# k1fm_wspr_tx-1_0.net
KiCad netlist of a schematic drawn in EAGLE
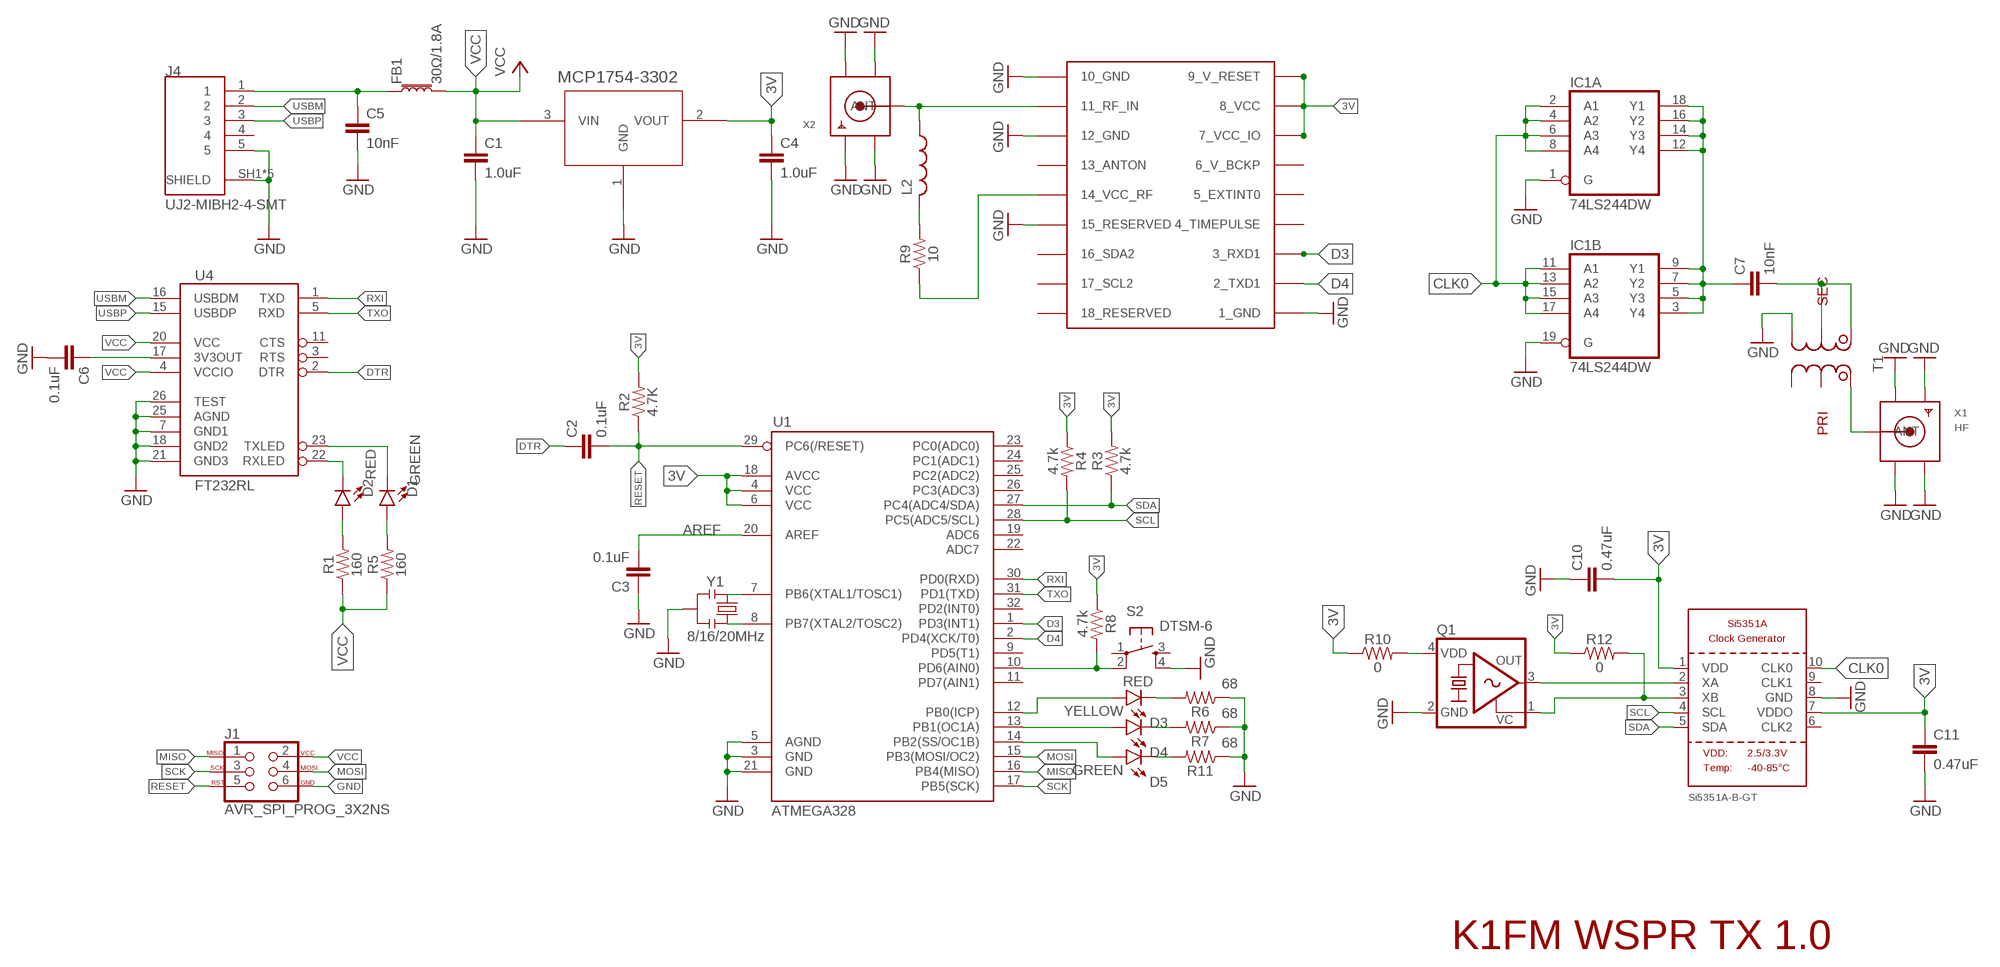
[diagram p0: schematic, sheet 1]

(export (version "E")
  (design (tool "Eeschema 10.0.6"))
  (components
    (comp (ref "C1")
      (value "1.0uF")
      (footprint "eagle-import:0603")
      (libsource (lib "eagle-import") (part "1.0UF-0603-16V-10%"))
    )
    (comp (ref "C2")
      (value "0.1uF")
      (footprint "eagle-import:0603")
      (libsource (lib "eagle-import") (part "0.1UF-0603-25V-5%"))
    )
    (comp (ref "C3")
      (value "0.1uF")
      (footprint "eagle-import:0603")
      (libsource (lib "eagle-import") (part "0.1UF-0603-25V-5%"))
    )
    (comp (ref "C4")
      (value "1.0uF")
      (footprint "eagle-import:0603")
      (libsource (lib "eagle-import") (part "1.0UF-0603-16V-10%"))
    )
    (comp (ref "C5")
      (value "10nF")
      (footprint "eagle-import:0603")
      (libsource (lib "eagle-import") (part "1.0UF-0603-16V-10%"))
    )
    (comp (ref "C6")
      (value "0.1uF")
      (footprint "eagle-import:0603")
      (libsource (lib "eagle-import") (part "0.1UF-0603-25V-5%"))
    )
    (comp (ref "C7")
      (value "10nF")
      (footprint "eagle-import:0603")
      (libsource (lib "eagle-import") (part "1.0UF-0603-16V-10%"))
    )
    (comp (ref "C10")
      (value "0.47uF")
      (footprint "eagle-import:0603")
      (libsource (lib "eagle-import") (part "0.1UF-0603-25V-5%"))
    )
    (comp (ref "C11")
      (value "0.47uF")
      (footprint "eagle-import:0603")
      (libsource (lib "eagle-import") (part "0.1UF-0603-25V-5%"))
    )
    (comp (ref "D1")
      (value "GREEN")
      (footprint "eagle-import:LED-0603")
      (libsource (lib "eagle-import") (part "LED0603"))
    )
    (comp (ref "D2")
      (value "RED")
      (footprint "eagle-import:LED-0603")
      (libsource (lib "eagle-import") (part "LED0603"))
    )
    (comp (ref "D3")
      (value "RED")
      (footprint "eagle-import:LED-0603")
      (libsource (lib "eagle-import") (part "LED0603"))
    )
    (comp (ref "D4")
      (value "YELLOW")
      (footprint "eagle-import:LED-0603")
      (libsource (lib "eagle-import") (part "LED0603"))
    )
    (comp (ref "D5")
      (value "GREEN")
      (footprint "eagle-import:LED-0603")
      (libsource (lib "eagle-import") (part "LED0603"))
    )
    (comp (ref "FB1")
      (value "30Ω/1.8A")
      (footprint "eagle-import:0603")
      (libsource (lib "eagle-import") (part "FERRITE_BEAD-0603"))
    )
    (comp (ref "GPS1")
      (value "UBLOX_MAX")
      (footprint "eagle-import:UBLOX_MAX")
      (libsource (lib "eagle-import") (part "UBLOX_MAX"))
    )
    (comp (ref "IC1")
      (value "74LS244DW")
      (footprint "eagle-import:SO20W")
      (libsource (lib "eagle-import") (part "74244DWLS"))
    )
    (comp (ref "J1")
      (value "AVR_SPI_PROG_3X2NS")
      (footprint "eagle-import:2X3-NS")
      (libsource (lib "eagle-import") (part "AVR_SPI_PROG_3X2NS"))
    )
    (comp (ref "J4")
      (value "UJ2-MIBH2-4-SMT")
      (footprint "eagle-import:CUI_UJ2-MIBH2-4-SMT")
      (fields (field (name "MANUFACTURER") "CUI INC"))
      (libsource (lib "eagle-import") (part "UJ2-MIBH2-4-SMT"))
    )
    (comp (ref "L2")
      (value "INDUCTOR_0402_M")
      (footprint "eagle-import:RESC0402_M")
      (libsource (lib "eagle-import") (part "INDUCTOR_0402_M"))
    )
    (comp (ref "Q1")
      (value "KXO-VCXO-SINE-84")
      (footprint "eagle-import:3.2X2.5_KXO-84")
      (libsource (lib "eagle-import") (part "KXO-VCXO-SINE-84"))
    )
    (comp (ref "R1")
      (value "160")
      (footprint "eagle-import:0603")
      (libsource (lib "eagle-import") (part "4.7KOHM-0603-1/10W-1%"))
    )
    (comp (ref "R2")
      (value "4.7K")
      (footprint "eagle-import:0603")
      (libsource (lib "eagle-import") (part "10KOHM-0603-1/10W-1%"))
    )
    (comp (ref "R3")
      (value "4.7k")
      (footprint "eagle-import:0603")
      (libsource (lib "eagle-import") (part "4.7KOHM-0603-1/10W-1%"))
    )
    (comp (ref "R4")
      (value "4.7k")
      (footprint "eagle-import:0603")
      (libsource (lib "eagle-import") (part "4.7KOHM-0603-1/10W-1%"))
    )
    (comp (ref "R5")
      (value "160")
      (footprint "eagle-import:0603")
      (libsource (lib "eagle-import") (part "4.7KOHM-0603-1/10W-1%"))
    )
    (comp (ref "R6")
      (value "68")
      (footprint "eagle-import:0603")
      (libsource (lib "eagle-import") (part "4.7KOHM-0603-1/10W-1%"))
    )
    (comp (ref "R7")
      (value "68")
      (footprint "eagle-import:0603")
      (libsource (lib "eagle-import") (part "4.7KOHM-0603-1/10W-1%"))
    )
    (comp (ref "R8")
      (value "4.7k")
      (footprint "eagle-import:0603")
      (libsource (lib "eagle-import") (part "4.7KOHM-0603-1/10W-1%"))
    )
    (comp (ref "R9")
      (value "10")
      (footprint "eagle-import:0603")
      (libsource (lib "eagle-import") (part "10KOHM-0603-1/10W-1%"))
    )
    (comp (ref "R10")
      (value "0")
      (footprint "eagle-import:0603")
      (libsource (lib "eagle-import") (part "4.7KOHM-0603-1/10W-1%"))
    )
    (comp (ref "R11")
      (value "68")
      (footprint "eagle-import:0603")
      (libsource (lib "eagle-import") (part "4.7KOHM-0603-1/10W-1%"))
    )
    (comp (ref "R12")
      (value "0")
      (footprint "eagle-import:0603")
      (libsource (lib "eagle-import") (part "4.7KOHM-0603-1/10W-1%"))
    )
    (comp (ref "S2")
      (value "DTSM-6")
      (footprint "eagle-import:DTSM-6")
      (libsource (lib "eagle-import") (part "DTSM-6"))
    )
    (comp (ref "T1")
      (value "TT1-6")
      (footprint "eagle-import:KK81")
      (libsource (lib "eagle-import") (part "TT1-6"))
    )
    (comp (ref "U1")
      (value "ATMEGA328")
      (footprint "eagle-import:TQFP32-08")
      (libsource (lib "eagle-import") (part "ATMEGA168"))
    )
    (comp (ref "U2")
      (value "Si5351A-B-GT")
      (footprint "eagle-import:MSOP10")
      (libsource (lib "eagle-import") (part "SI5351A"))
    )
    (comp (ref "U3")
      (value "MCP1754X-XXXXX/C")
      (footprint "eagle-import:SOT-23A_MC")
      (libsource (lib "eagle-import") (part "MCP1754X-XXXXX/C"))
    )
    (comp (ref "U4")
      (value "FT232RL")
      (footprint "eagle-import:SSOP28DB")
      (libsource (lib "eagle-import") (part "FT232RL-BASICSSOP"))
    )
    (comp (ref "X1")
      (value "HF")
      (footprint "eagle-import:SMA_EDGELAUNCH")
      (libsource (lib "eagle-import") (part "SMACONNECTOR_EDGE"))
    )
    (comp (ref "X2")
      (value "SMACONNECTOR_EDGE")
      (footprint "eagle-import:SMA_EDGELAUNCH")
      (libsource (lib "eagle-import") (part "SMACONNECTOR_EDGE"))
    )
    (comp (ref "Y1")
      (value "8/16/20MHz")
      (footprint "eagle-import:RESONATOR-SMD-1_1")
      (libsource (lib "eagle-import") (part "RESONATOR1{colon}1"))
    )
  )
  (nets
    (net (code "1") (name "/AREF") (class "Default")
      (node (ref "C3") (pin "2") (pinfunction "2_2") (pintype "passive"))
      (node (ref "U1") (pin "20") (pinfunction "AREF_20") (pintype "bidirectional"))
    )
    (net (code "2") (name "3V") (class "Default")
      (node (ref "C10") (pin "2") (pinfunction "2_2") (pintype "passive"))
      (node (ref "C11") (pin "1") (pinfunction "1_1") (pintype "passive"))
      (node (ref "C4") (pin "1") (pinfunction "1_1") (pintype "passive"))
      (node (ref "GPS1") (pin "7_VCC_IO") (pinfunction "7_VCC_IO_7_VCC_IO") (pintype "power_in"))
      (node (ref "GPS1") (pin "8_VCC") (pinfunction "8_VCC_8_VCC") (pintype "power_in"))
      (node (ref "GPS1") (pin "9_V_RESET") (pinfunction "9_V_RESET_9_V_RESET") (pintype "power_in"))
      (node (ref "R10") (pin "1") (pinfunction "1_1") (pintype "passive"))
      (node (ref "R12") (pin "1") (pinfunction "1_1") (pintype "passive"))
      (node (ref "R2") (pin "2") (pinfunction "2_2") (pintype "passive"))
      (node (ref "R3") (pin "2") (pinfunction "2_2") (pintype "passive"))
      (node (ref "R4") (pin "1") (pinfunction "1_1") (pintype "passive"))
      (node (ref "R8") (pin "1") (pinfunction "1_1") (pintype "passive"))
      (node (ref "U1") (pin "18") (pinfunction "AVCC_18") (pintype "bidirectional"))
      (node (ref "U1") (pin "4") (pinfunction "VCC_4") (pintype "bidirectional"))
      (node (ref "U1") (pin "6") (pinfunction "VCC_6") (pintype "bidirectional"))
      (node (ref "U2") (pin "1") (pinfunction "VDD_1") (pintype "power_in"))
      (node (ref "U2") (pin "7") (pinfunction "VDDO_7") (pintype "power_in"))
      (node (ref "U3") (pin "2") (pinfunction "VOUT_2") (pintype "passive"))
    )
    (net (code "3") (name "CLK0") (class "Default")
      (node (ref "IC1") (pin "11") (pinfunction "A1_11") (pintype "input"))
      (node (ref "IC1") (pin "13") (pinfunction "A2_13") (pintype "input"))
      (node (ref "IC1") (pin "15") (pinfunction "A3_15") (pintype "input"))
      (node (ref "IC1") (pin "17") (pinfunction "A4_17") (pintype "input"))
      (node (ref "IC1") (pin "2") (pinfunction "A1_2") (pintype "input"))
      (node (ref "IC1") (pin "4") (pinfunction "A2_4") (pintype "input"))
      (node (ref "IC1") (pin "6") (pinfunction "A3_6") (pintype "input"))
      (node (ref "IC1") (pin "8") (pinfunction "A4_8") (pintype "input"))
      (node (ref "U2") (pin "10") (pinfunction "CLK0_10") (pintype "output"))
    )
    (net (code "4") (name "D3") (class "Default")
      (node (ref "GPS1") (pin "3_RXD1") (pinfunction "3_RXD1_3_RXD1") (pintype "bidirectional"))
      (node (ref "U1") (pin "1") (pinfunction "PD3(INT1)_1") (pintype "bidirectional"))
    )
    (net (code "5") (name "D4") (class "Default")
      (node (ref "GPS1") (pin "2_TXD1") (pinfunction "2_TXD1_2_TXD1") (pintype "bidirectional"))
      (node (ref "U1") (pin "2") (pinfunction "PD4(XCK/T0)_2") (pintype "bidirectional"))
    )
    (net (code "6") (name "DTR") (class "Default")
      (node (ref "C2") (pin "1") (pinfunction "1_1") (pintype "passive"))
      (node (ref "U4") (pin "2") (pinfunction "DTR_2") (pintype "bidirectional"))
    )
    (net (code "7") (name "GND") (class "Default")
      (node (ref "C1") (pin "2") (pinfunction "2_2") (pintype "passive"))
      (node (ref "C10") (pin "1") (pinfunction "1_1") (pintype "passive"))
      (node (ref "C11") (pin "2") (pinfunction "2_2") (pintype "passive"))
      (node (ref "C3") (pin "1") (pinfunction "1_1") (pintype "passive"))
      (node (ref "C4") (pin "2") (pinfunction "2_2") (pintype "passive"))
      (node (ref "C5") (pin "2") (pinfunction "2_2") (pintype "passive"))
      (node (ref "C6") (pin "2") (pinfunction "2_2") (pintype "passive"))
      (node (ref "GPS1") (pin "10_GND") (pinfunction "10_GND_10_GND") (pintype "power_in"))
      (node (ref "GPS1") (pin "12_GND") (pinfunction "12_GND_12_GND") (pintype "power_in"))
      (node (ref "GPS1") (pin "15_RESERVED") (pinfunction "15_RESERVED_15_RESERVED") (pintype "bidirectional"))
      (node (ref "GPS1") (pin "1_GND") (pinfunction "1_GND_1_GND") (pintype "power_in"))
      (node (ref "IC1") (pin "1") (pinfunction "G_1") (pintype "input"))
      (node (ref "IC1") (pin "19") (pinfunction "G_19") (pintype "input"))
      (node (ref "J1") (pin "6") (pinfunction "6_6") (pintype "passive"))
      (node (ref "J4") (pin "5") (pinfunction "5_5") (pintype "passive"))
      (node (ref "J4") (pin "SH1") (pinfunction "SHIELD_SH1") (pintype "passive"))
      (node (ref "J4") (pin "SH2") (pinfunction "SHIELD_SH2") (pintype "passive"))
      (node (ref "J4") (pin "SH3") (pinfunction "SHIELD_SH3") (pintype "passive"))
      (node (ref "J4") (pin "SH4") (pinfunction "SHIELD_SH4") (pintype "passive"))
      (node (ref "J4") (pin "SH5") (pinfunction "SHIELD_SH5") (pintype "passive"))
      (node (ref "Q1") (pin "2") (pinfunction "GND_2") (pintype "power_in"))
      (node (ref "R11") (pin "1") (pinfunction "1_1") (pintype "passive"))
      (node (ref "R6") (pin "1") (pinfunction "1_1") (pintype "passive"))
      (node (ref "R7") (pin "1") (pinfunction "1_1") (pintype "passive"))
      (node (ref "S2") (pin "4") (pinfunction "4_4") (pintype "passive"))
      (node (ref "T1") (pin "1") (pinfunction "S2_1") (pintype "passive"))
      (node (ref "U1") (pin "21") (pinfunction "GND_21") (pintype "bidirectional"))
      (node (ref "U1") (pin "3") (pinfunction "GND_3") (pintype "bidirectional"))
      (node (ref "U1") (pin "5") (pinfunction "AGND_5") (pintype "bidirectional"))
      (node (ref "U2") (pin "8") (pinfunction "GND_8") (pintype "power_in"))
      (node (ref "U3") (pin "1") (pinfunction "GND_1") (pintype "passive"))
      (node (ref "U4") (pin "18") (pinfunction "GND2_18") (pintype "power_in"))
      (node (ref "U4") (pin "21") (pinfunction "GND3_21") (pintype "power_in"))
      (node (ref "U4") (pin "25") (pinfunction "AGND_25") (pintype "power_in"))
      (node (ref "U4") (pin "26") (pinfunction "TEST_26") (pintype "input"))
      (node (ref "U4") (pin "7") (pinfunction "GND1_7") (pintype "power_in"))
      (node (ref "X1") (pin "GND@1") (pinfunction "GND4_GND@1") (pintype "power_in"))
      (node (ref "X1") (pin "GND@2") (pinfunction "GND3_GND@2") (pintype "power_in"))
      (node (ref "X1") (pin "GND@3") (pinfunction "GND2_GND@3") (pintype "power_in"))
      (node (ref "X1") (pin "GND@4") (pinfunction "GND1_GND@4") (pintype "power_in"))
      (node (ref "X2") (pin "GND@1") (pinfunction "GND4_GND@1") (pintype "power_in"))
      (node (ref "X2") (pin "GND@2") (pinfunction "GND3_GND@2") (pintype "power_in"))
      (node (ref "X2") (pin "GND@3") (pinfunction "GND2_GND@3") (pintype "power_in"))
      (node (ref "X2") (pin "GND@4") (pinfunction "GND1_GND@4") (pintype "power_in"))
      (node (ref "Y1") (pin "2") (pinfunction "2_2") (pintype "passive"))
    )
    (net (code "8") (name "MISO") (class "Default")
      (node (ref "J1") (pin "1") (pinfunction "1_1") (pintype "passive"))
      (node (ref "U1") (pin "16") (pinfunction "PB4(MISO)_16") (pintype "bidirectional"))
    )
    (net (code "9") (name "MOSI") (class "Default")
      (node (ref "J1") (pin "4") (pinfunction "4_4") (pintype "passive"))
      (node (ref "U1") (pin "15") (pinfunction "PB3(MOSI/OC2)_15") (pintype "bidirectional"))
    )
    (net (code "10") (name "Net-(C5-Pad1)") (class "Default")
      (node (ref "C5") (pin "1") (pinfunction "1_1") (pintype "passive"))
      (node (ref "FB1") (pin "1") (pinfunction "1_1") (pintype "passive"))
      (node (ref "J4") (pin "1") (pinfunction "1_1") (pintype "passive"))
    )
    (net (code "11") (name "Net-(D1-PadA)") (class "Default")
      (node (ref "D1") (pin "A") (pinfunction "A_A") (pintype "passive"))
      (node (ref "R5") (pin "2") (pinfunction "2_2") (pintype "passive"))
    )
    (net (code "12") (name "Net-(D2-PadA)") (class "Default")
      (node (ref "D2") (pin "A") (pinfunction "A_A") (pintype "passive"))
      (node (ref "R1") (pin "2") (pinfunction "2_2") (pintype "passive"))
    )
    (net (code "13") (name "Net-(D3-PadC)") (class "Default")
      (node (ref "D3") (pin "C") (pinfunction "C_C") (pintype "passive"))
      (node (ref "R6") (pin "2") (pinfunction "2_2") (pintype "passive"))
    )
    (net (code "14") (name "Net-(D4-PadC)") (class "Default")
      (node (ref "D4") (pin "C") (pinfunction "C_C") (pintype "passive"))
      (node (ref "R7") (pin "2") (pinfunction "2_2") (pintype "passive"))
    )
    (net (code "15") (name "Net-(D5-PadC)") (class "Default")
      (node (ref "D5") (pin "C") (pinfunction "C_C") (pintype "passive"))
      (node (ref "R11") (pin "2") (pinfunction "2_2") (pintype "passive"))
    )
    (net (code "16") (name "Net-(GPS1-Pad14_VCC_RF)") (class "Default")
      (node (ref "GPS1") (pin "14_VCC_RF") (pinfunction "14_VCC_RF_14_VCC_RF") (pintype "bidirectional"))
      (node (ref "R9") (pin "1") (pinfunction "1_1") (pintype "passive"))
    )
    (net (code "17") (name "Net-(IC1A-Y1)") (class "Default")
      (node (ref "C7") (pin "1") (pinfunction "1_1") (pintype "passive"))
      (node (ref "IC1") (pin "12") (pinfunction "Y4_12") (pintype "tri_state"))
      (node (ref "IC1") (pin "14") (pinfunction "Y3_14") (pintype "tri_state"))
      (node (ref "IC1") (pin "16") (pinfunction "Y2_16") (pintype "tri_state"))
      (node (ref "IC1") (pin "18") (pinfunction "Y1_18") (pintype "tri_state"))
      (node (ref "IC1") (pin "3") (pinfunction "Y4_3") (pintype "tri_state"))
      (node (ref "IC1") (pin "5") (pinfunction "Y3_5") (pintype "tri_state"))
      (node (ref "IC1") (pin "7") (pinfunction "Y2_7") (pintype "tri_state"))
      (node (ref "IC1") (pin "9") (pinfunction "Y1_9") (pintype "tri_state"))
    )
    (net (code "18") (name "Net-(L2-Pad2)") (class "Default")
      (node (ref "L2") (pin "2") (pinfunction "2_2") (pintype "passive"))
      (node (ref "R9") (pin "2") (pinfunction "2_2") (pintype "passive"))
    )
    (net (code "19") (name "Net-(Q1-OUT)") (class "Default")
      (node (ref "Q1") (pin "3") (pinfunction "OUT_3") (pintype "output"))
      (node (ref "U2") (pin "2") (pinfunction "XA_2") (pintype "input"))
    )
    (net (code "20") (name "Net-(Q1-VC)") (class "Default")
      (node (ref "Q1") (pin "1") (pinfunction "VC_1") (pintype "input"))
      (node (ref "R12") (pin "2") (pinfunction "2_2") (pintype "passive"))
      (node (ref "U2") (pin "3") (pinfunction "XB_3") (pintype "input"))
    )
    (net (code "21") (name "Net-(Q1-VDD)") (class "Default")
      (node (ref "Q1") (pin "4") (pinfunction "VDD_4") (pintype "power_in"))
      (node (ref "R10") (pin "2") (pinfunction "2_2") (pintype "passive"))
    )
    (net (code "22") (name "Net-(T1-P1)") (class "Default")
      (node (ref "T1") (pin "4") (pinfunction "P1_4") (pintype "passive"))
      (node (ref "X1") (pin "P") (pinfunction "ANT_P") (pintype "bidirectional"))
    )
    (net (code "23") (name "Net-(T1-S1)") (class "Default")
      (node (ref "C7") (pin "2") (pinfunction "2_2") (pintype "passive"))
      (node (ref "T1") (pin "2") (pinfunction "ST_2") (pintype "passive"))
      (node (ref "T1") (pin "3") (pinfunction "S1_3") (pintype "passive"))
    )
    (net (code "24") (name "Net-(U1-PB0(ICP))") (class "Default")
      (node (ref "D3") (pin "A") (pinfunction "A_A") (pintype "passive"))
      (node (ref "U1") (pin "12") (pinfunction "PB0(ICP)_12") (pintype "bidirectional"))
    )
    (net (code "25") (name "Net-(U1-PB1(OC1A))") (class "Default")
      (node (ref "D4") (pin "A") (pinfunction "A_A") (pintype "passive"))
      (node (ref "U1") (pin "13") (pinfunction "PB1(OC1A)_13") (pintype "bidirectional"))
    )
    (net (code "26") (name "Net-(U1-PB2(SS{slash}OC1B))") (class "Default")
      (node (ref "D5") (pin "A") (pinfunction "A_A") (pintype "passive"))
      (node (ref "U1") (pin "14") (pinfunction "PB2(SS/OC1B)_14") (pintype "bidirectional"))
    )
    (net (code "27") (name "Net-(U1-PB6(XTAL1{slash}TOSC1))") (class "Default")
      (node (ref "U1") (pin "7") (pinfunction "PB6(XTAL1/TOSC1)_7") (pintype "bidirectional"))
      (node (ref "Y1") (pin "1") (pinfunction "1_1") (pintype "passive"))
    )
    (net (code "28") (name "Net-(U1-PB7(XTAL2{slash}TOSC2))") (class "Default")
      (node (ref "U1") (pin "8") (pinfunction "PB7(XTAL2/TOSC2)_8") (pintype "bidirectional"))
      (node (ref "Y1") (pin "3") (pinfunction "3_3") (pintype "passive"))
    )
    (net (code "29") (name "Net-(U1-PD6(AIN0))") (class "Default")
      (node (ref "R8") (pin "2") (pinfunction "2_2") (pintype "passive"))
      (node (ref "S2") (pin "2") (pinfunction "2_2") (pintype "passive"))
      (node (ref "U1") (pin "10") (pinfunction "PD6(AIN0)_10") (pintype "bidirectional"))
    )
    (net (code "30") (name "Net-(U4-3V3OUT)") (class "Default")
      (node (ref "C6") (pin "1") (pinfunction "1_1") (pintype "passive"))
      (node (ref "U4") (pin "17") (pinfunction "3V3OUT_17") (pintype "output"))
    )
    (net (code "31") (name "Net-(U4-RXLED)") (class "Default")
      (node (ref "D2") (pin "C") (pinfunction "C_C") (pintype "passive"))
      (node (ref "U4") (pin "22") (pinfunction "RXLED_22") (pintype "bidirectional"))
    )
    (net (code "32") (name "Net-(U4-TXLED)") (class "Default")
      (node (ref "D1") (pin "C") (pinfunction "C_C") (pintype "passive"))
      (node (ref "U4") (pin "23") (pinfunction "TXLED_23") (pintype "bidirectional"))
    )
    (net (code "33") (name "Net-(X2-ANT)") (class "Default")
      (node (ref "GPS1") (pin "11_RF_IN") (pinfunction "11_RF_IN_11_RF_IN") (pintype "bidirectional"))
      (node (ref "L2") (pin "1") (pinfunction "1_1") (pintype "passive"))
      (node (ref "X2") (pin "P") (pinfunction "ANT_P") (pintype "bidirectional"))
    )
    (net (code "34") (name "RESET") (class "Default")
      (node (ref "C2") (pin "2") (pinfunction "2_2") (pintype "passive"))
      (node (ref "J1") (pin "5") (pinfunction "5_5") (pintype "passive"))
      (node (ref "R2") (pin "1") (pinfunction "1_1") (pintype "passive"))
      (node (ref "U1") (pin "29") (pinfunction "PC6(/RESET)_29") (pintype "bidirectional"))
    )
    (net (code "35") (name "RXI") (class "Default")
      (node (ref "U1") (pin "30") (pinfunction "PD0(RXD)_30") (pintype "bidirectional"))
      (node (ref "U4") (pin "1") (pinfunction "TXD_1") (pintype "output"))
    )
    (net (code "36") (name "SCK") (class "Default")
      (node (ref "J1") (pin "3") (pinfunction "3_3") (pintype "passive"))
      (node (ref "U1") (pin "17") (pinfunction "PB5(SCK)_17") (pintype "bidirectional"))
    )
    (net (code "37") (name "SCL") (class "Default")
      (node (ref "R4") (pin "2") (pinfunction "2_2") (pintype "passive"))
      (node (ref "U1") (pin "28") (pinfunction "PC5(ADC5/SCL)_28") (pintype "bidirectional"))
      (node (ref "U2") (pin "4") (pinfunction "SCL_4") (pintype "input"))
    )
    (net (code "38") (name "SDA") (class "Default")
      (node (ref "R3") (pin "1") (pinfunction "1_1") (pintype "passive"))
      (node (ref "U1") (pin "27") (pinfunction "PC4(ADC4/SDA)_27") (pintype "bidirectional"))
      (node (ref "U2") (pin "5") (pinfunction "SDA_5") (pintype "bidirectional"))
    )
    (net (code "39") (name "TXO") (class "Default")
      (node (ref "U1") (pin "31") (pinfunction "PD1(TXD)_31") (pintype "bidirectional"))
      (node (ref "U4") (pin "5") (pinfunction "RXD_5") (pintype "input"))
    )
    (net (code "40") (name "USBM") (class "Default")
      (node (ref "J4") (pin "2") (pinfunction "2_2") (pintype "passive"))
      (node (ref "U4") (pin "16") (pinfunction "USBDM_16") (pintype "bidirectional"))
    )
    (net (code "41") (name "USBP") (class "Default")
      (node (ref "J4") (pin "3") (pinfunction "3_3") (pintype "passive"))
      (node (ref "U4") (pin "15") (pinfunction "USBDP_15") (pintype "bidirectional"))
    )
    (net (code "42") (name "VCC") (class "Default")
      (node (ref "C1") (pin "1") (pinfunction "1_1") (pintype "passive"))
      (node (ref "FB1") (pin "2") (pinfunction "2_2") (pintype "passive"))
      (node (ref "J1") (pin "2") (pinfunction "2_2") (pintype "passive"))
      (node (ref "R1") (pin "1") (pinfunction "1_1") (pintype "passive"))
      (node (ref "R5") (pin "1") (pinfunction "1_1") (pintype "passive"))
      (node (ref "U3") (pin "3") (pinfunction "VIN_3") (pintype "passive"))
      (node (ref "U4") (pin "20") (pinfunction "VCC_20") (pintype "power_in"))
      (node (ref "U4") (pin "4") (pinfunction "VCCIO_4") (pintype "power_in"))
    )
    (net (code "43") (name "unconnected-(GPS1-Pad4_TIMEPULSE)") (class "Default")
      (node (ref "GPS1") (pin "4_TIMEPULSE") (pinfunction "4_TIMEPULSE_4_TIMEPULSE") (pintype "bidirectional"))
    )
    (net (code "44") (name "unconnected-(GPS1-Pad5_EXTINT0)") (class "Default")
      (node (ref "GPS1") (pin "5_EXTINT0") (pinfunction "5_EXTINT0_5_EXTINT0") (pintype "bidirectional"))
    )
    (net (code "45") (name "unconnected-(GPS1-Pad6_V_BCKP)") (class "Default")
      (node (ref "GPS1") (pin "6_V_BCKP") (pinfunction "6_V_BCKP_6_V_BCKP") (pintype "bidirectional"))
    )
    (net (code "46") (name "unconnected-(GPS1-Pad13_ANTON)") (class "Default")
      (node (ref "GPS1") (pin "13_ANTON") (pinfunction "13_ANTON_13_ANTON") (pintype "bidirectional"))
    )
    (net (code "47") (name "unconnected-(GPS1-Pad16_SDA2)") (class "Default")
      (node (ref "GPS1") (pin "16_SDA2") (pinfunction "16_SDA2_16_SDA2") (pintype "bidirectional"))
    )
    (net (code "48") (name "unconnected-(GPS1-Pad17_SCL2)") (class "Default")
      (node (ref "GPS1") (pin "17_SCL2") (pinfunction "17_SCL2_17_SCL2") (pintype "bidirectional"))
    )
    (net (code "49") (name "unconnected-(GPS1-Pad18_RESERVED)") (class "Default")
      (node (ref "GPS1") (pin "18_RESERVED") (pinfunction "18_RESERVED_18_RESERVED") (pintype "bidirectional"))
    )
    (net (code "50") (name "unconnected-(J4-Pad4)") (class "Default")
      (node (ref "J4") (pin "4") (pinfunction "4_4") (pintype "passive"))
    )
    (net (code "51") (name "unconnected-(S2-Pad1)") (class "Default")
      (node (ref "S2") (pin "1") (pinfunction "1_1") (pintype "passive"))
    )
    (net (code "52") (name "unconnected-(S2-Pad3)") (class "Default")
      (node (ref "S2") (pin "3") (pinfunction "3_3") (pintype "passive"))
    )
    (net (code "53") (name "unconnected-(T1-P2-Pad6)") (class "Default")
      (node (ref "T1") (pin "6") (pinfunction "P2_6") (pintype "passive"))
    )
    (net (code "54") (name "unconnected-(T1-PT-Pad5)") (class "Default")
      (node (ref "T1") (pin "5") (pinfunction "PT_5") (pintype "passive"))
    )
    (net (code "55") (name "unconnected-(U1-ADC6-Pad19)") (class "Default")
      (node (ref "U1") (pin "19") (pinfunction "ADC6_19") (pintype "bidirectional"))
    )
    (net (code "56") (name "unconnected-(U1-ADC7-Pad22)") (class "Default")
      (node (ref "U1") (pin "22") (pinfunction "ADC7_22") (pintype "bidirectional"))
    )
    (net (code "57") (name "unconnected-(U1-PC0(ADC0)-Pad23)") (class "Default")
      (node (ref "U1") (pin "23") (pinfunction "PC0(ADC0)_23") (pintype "bidirectional"))
    )
    (net (code "58") (name "unconnected-(U1-PC1(ADC1)-Pad24)") (class "Default")
      (node (ref "U1") (pin "24") (pinfunction "PC1(ADC1)_24") (pintype "bidirectional"))
    )
    (net (code "59") (name "unconnected-(U1-PC2(ADC2)-Pad25)") (class "Default")
      (node (ref "U1") (pin "25") (pinfunction "PC2(ADC2)_25") (pintype "bidirectional"))
    )
    (net (code "60") (name "unconnected-(U1-PC3(ADC3)-Pad26)") (class "Default")
      (node (ref "U1") (pin "26") (pinfunction "PC3(ADC3)_26") (pintype "bidirectional"))
    )
    (net (code "61") (name "unconnected-(U1-PD2(INT0)-Pad32)") (class "Default")
      (node (ref "U1") (pin "32") (pinfunction "PD2(INT0)_32") (pintype "bidirectional"))
    )
    (net (code "62") (name "unconnected-(U1-PD5(T1)-Pad9)") (class "Default")
      (node (ref "U1") (pin "9") (pinfunction "PD5(T1)_9") (pintype "bidirectional"))
    )
    (net (code "63") (name "unconnected-(U1-PD7(AIN1)-Pad11)") (class "Default")
      (node (ref "U1") (pin "11") (pinfunction "PD7(AIN1)_11") (pintype "bidirectional"))
    )
    (net (code "64") (name "unconnected-(U2-CLK1-Pad9)") (class "Default")
      (node (ref "U2") (pin "9") (pinfunction "CLK1_9") (pintype "output"))
    )
    (net (code "65") (name "unconnected-(U2-CLK2-Pad6)") (class "Default")
      (node (ref "U2") (pin "6") (pinfunction "CLK2_6") (pintype "output"))
    )
    (net (code "66") (name "unconnected-(U4-CTS-Pad11)") (class "Default")
      (node (ref "U4") (pin "11") (pinfunction "CTS_11") (pintype "bidirectional"))
    )
    (net (code "67") (name "unconnected-(U4-RTS-Pad3)") (class "Default")
      (node (ref "U4") (pin "3") (pinfunction "RTS_3") (pintype "bidirectional"))
    )
  )
)
